# LCDTFT_CTRL_BT817.net
KiCad netlist of a schematic drawn in Altium Designer
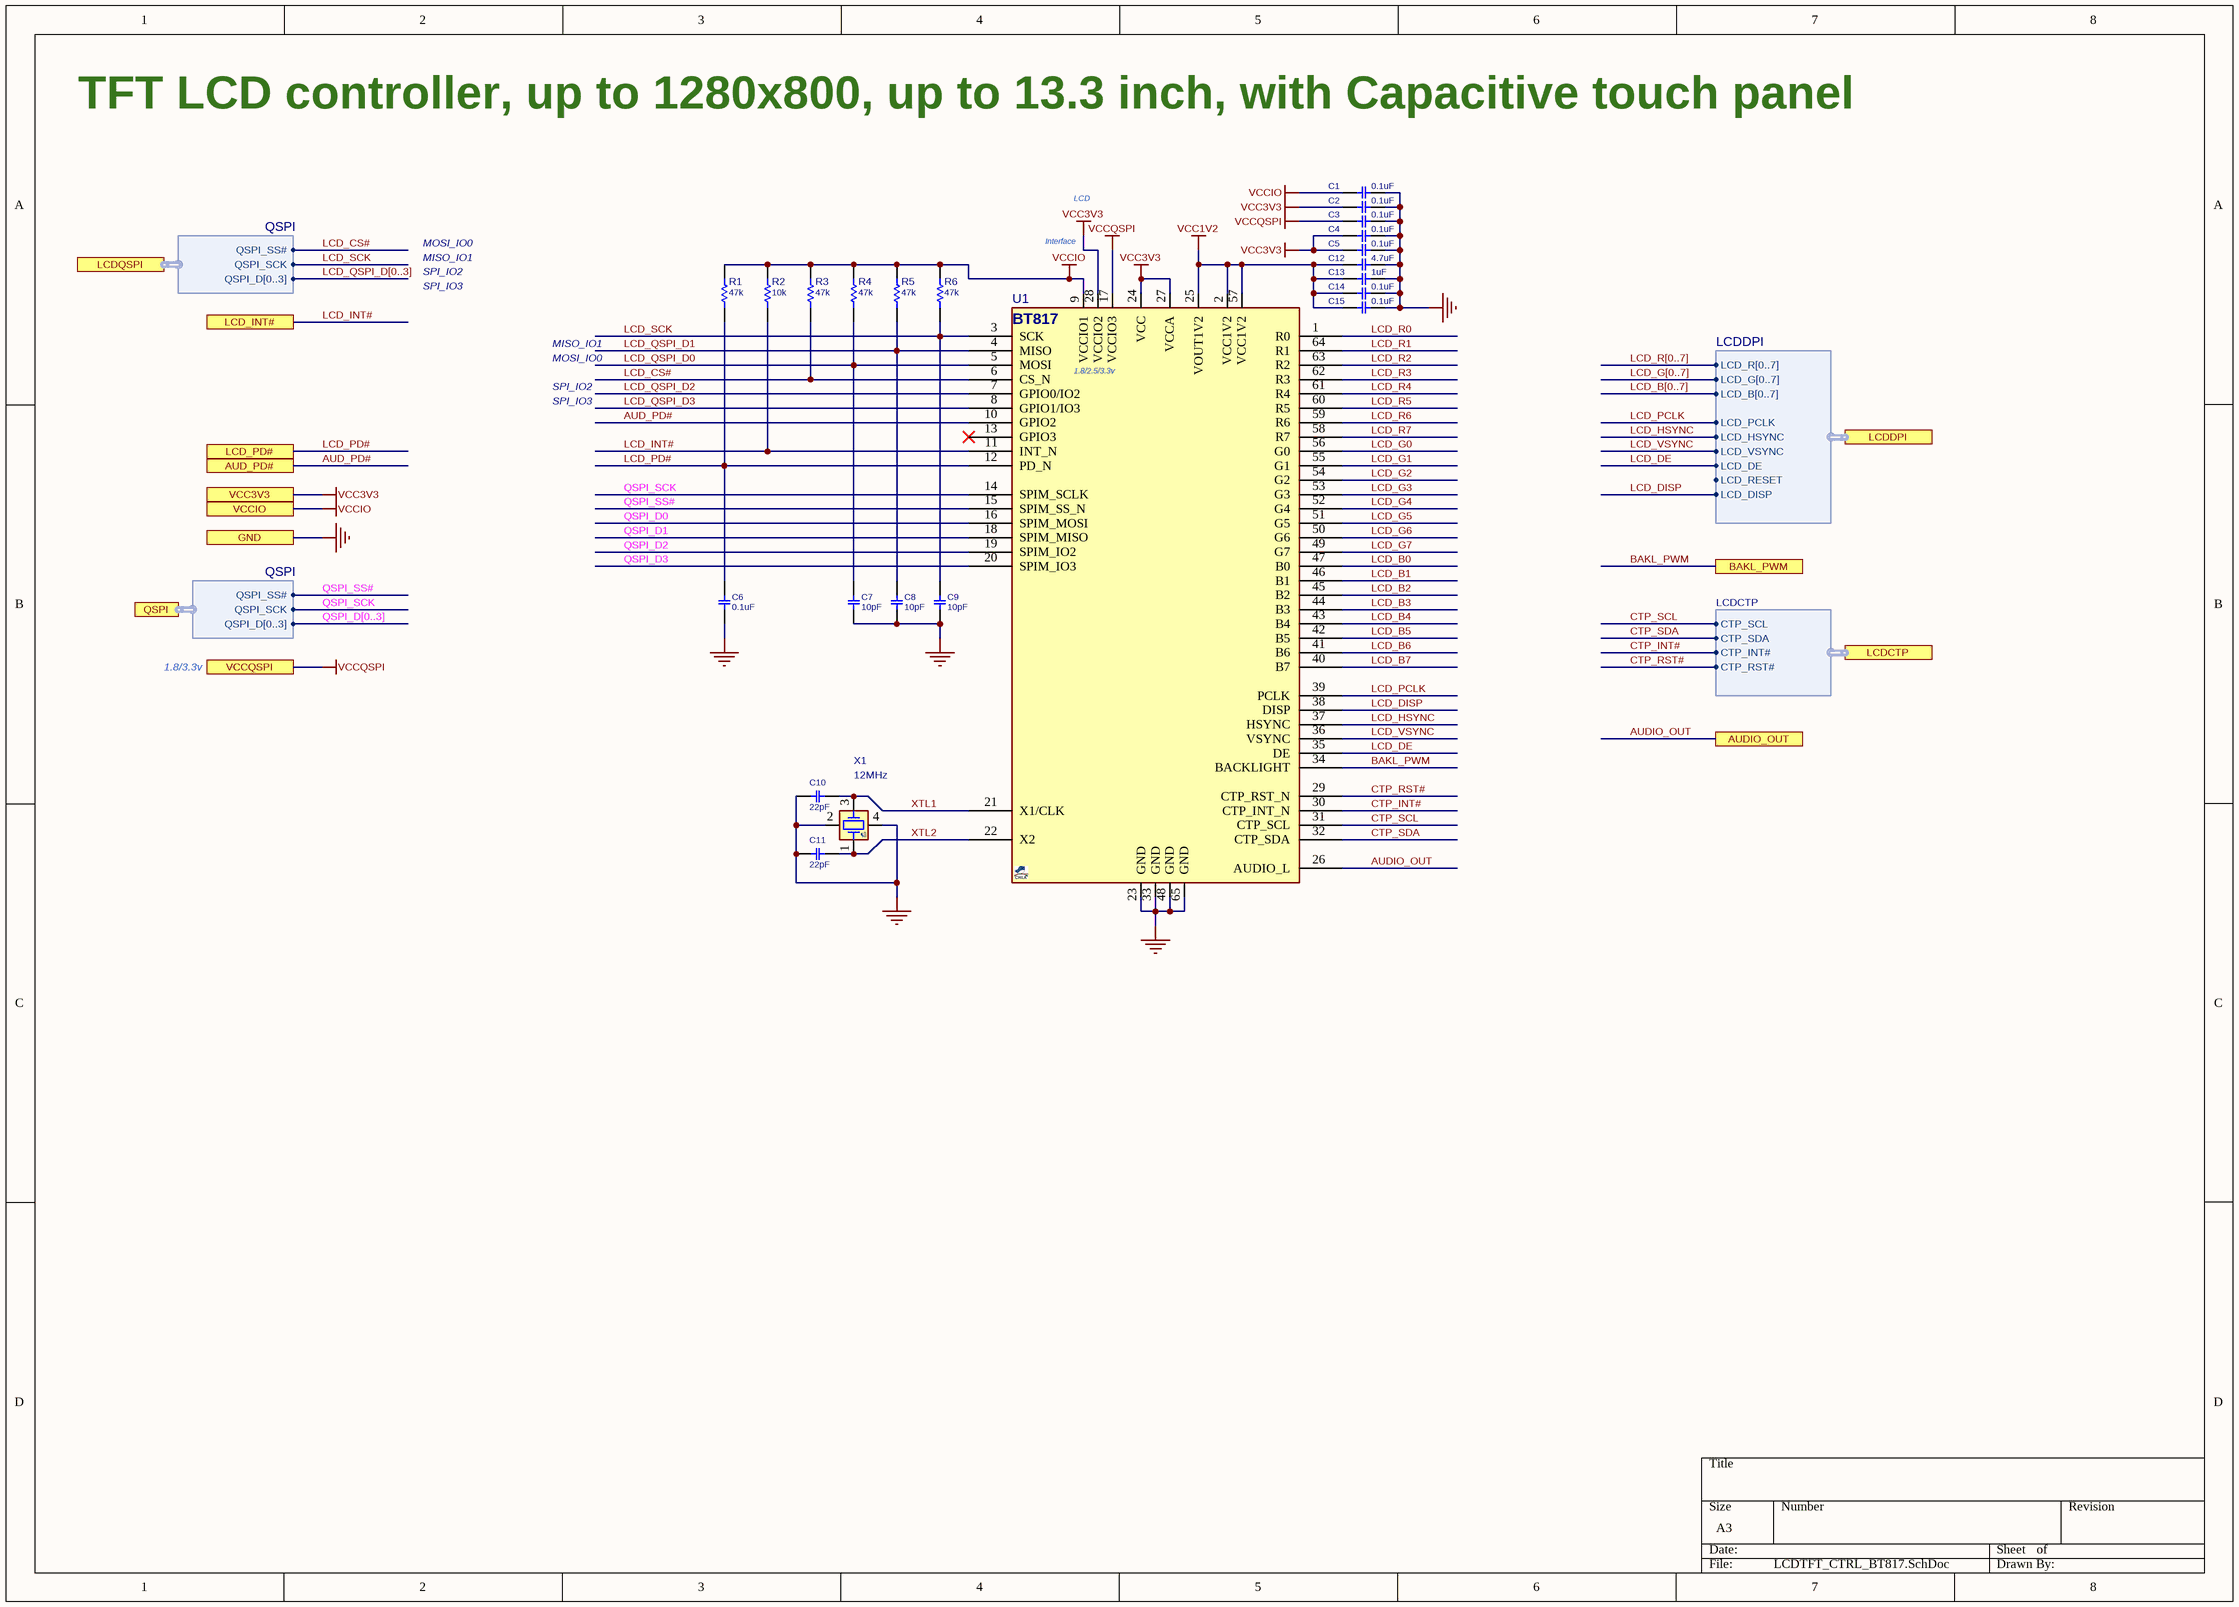
[diagram p0: LCDTFT_CTRL_BT817.SchDoc]

(export (version "E")
  (design (tool "Eeschema 10.0.6"))
  (components
    (comp (ref "C1")
      (value "0.1uF")
      (footprint "C0402")
      (description "CAP, MLCC")
      (fields (field (name "MANF_P#") "GRM155R71H104KE14D") (field (name "MANF") "Murata"))
      (libsource (lib "passive_smd") (part "CAP_SMD_MLCC"))
    )
    (comp (ref "C2")
      (value "0.1uF")
      (footprint "C0402")
      (description "CAP, MLCC")
      (fields (field (name "MANF_P#") "GRM155R71H104KE14D") (field (name "MANF") "Murata"))
      (libsource (lib "passive_smd") (part "CAP_SMD_MLCC"))
    )
    (comp (ref "C3")
      (value "0.1uF")
      (footprint "C0402")
      (description "CAP, MLCC")
      (fields (field (name "MANF_P#") "GRM155R71H104KE14D") (field (name "MANF") "Murata"))
      (libsource (lib "passive_smd") (part "CAP_SMD_MLCC"))
    )
    (comp (ref "C4")
      (value "0.1uF")
      (footprint "C0402")
      (description "CAP, MLCC")
      (fields (field (name "MANF_P#") "GRM155R71H104KE14D") (field (name "MANF") "Murata"))
      (libsource (lib "passive_smd") (part "CAP_SMD_MLCC"))
    )
    (comp (ref "C5")
      (value "0.1uF")
      (footprint "C0402")
      (description "CAP, MLCC")
      (fields (field (name "MANF_P#") "GRM155R71H104KE14D") (field (name "MANF") "Murata"))
      (libsource (lib "passive_smd") (part "CAP_SMD_MLCC"))
    )
    (comp (ref "C6")
      (value "0.1uF")
      (footprint "C0402")
      (description "CAP, MLCC")
      (fields (field (name "MANF_P#") "GRM155R71H104KE14D") (field (name "MANF") "Murata"))
      (libsource (lib "passive_smd") (part "CAP_SMD_MLCC"))
    )
    (comp (ref "C7")
      (value "10pF")
      (footprint "C0402")
      (description "CAP, MLCC")
      (libsource (lib "passive_smd") (part "CAP_SMD_MLCC"))
    )
    (comp (ref "C8")
      (value "10pF")
      (footprint "C0402")
      (description "CAP, MLCC")
      (libsource (lib "passive_smd") (part "CAP_SMD_MLCC"))
    )
    (comp (ref "C9")
      (value "10pF")
      (footprint "C0402")
      (description "CAP, MLCC")
      (libsource (lib "passive_smd") (part "CAP_SMD_MLCC"))
    )
    (comp (ref "C10")
      (value "22pF")
      (footprint "C0402")
      (description "CAP, MLCC")
      (libsource (lib "passive_smd") (part "CAP_SMD_MLCC"))
    )
    (comp (ref "C11")
      (value "22pF")
      (footprint "C0402")
      (description "CAP, MLCC")
      (libsource (lib "passive_smd") (part "CAP_SMD_MLCC"))
    )
    (comp (ref "C12")
      (value "4.7uF")
      (footprint "C0402")
      (description "CAP, MLCC")
      (libsource (lib "passive_smd") (part "CAP_SMD_MLCC"))
    )
    (comp (ref "C13")
      (value "1uF")
      (footprint "C0402")
      (description "CAP, MLCC")
      (libsource (lib "passive_smd") (part "CAP_SMD_MLCC"))
    )
    (comp (ref "C14")
      (value "0.1uF")
      (footprint "C0402")
      (description "CAP, MLCC")
      (fields (field (name "MANF_P#") "GRM155R71H104KE14D") (field (name "MANF") "Murata"))
      (libsource (lib "passive_smd") (part "CAP_SMD_MLCC"))
    )
    (comp (ref "C15")
      (value "0.1uF")
      (footprint "C0402")
      (description "CAP, MLCC")
      (fields (field (name "MANF_P#") "GRM155R71H104KE14D") (field (name "MANF") "Murata"))
      (libsource (lib "passive_smd") (part "CAP_SMD_MLCC"))
    )
    (comp (ref "R1")
      (value "47k")
      (footprint "R0402")
      (description "RESISTOR, SMD")
      (libsource (lib "passive_res_smd") (part "RES_SMD"))
    )
    (comp (ref "R2")
      (value "10k")
      (footprint "R0402")
      (description "RESISTOR, SMD")
      (libsource (lib "passive_res_smd") (part "RES_SMD"))
    )
    (comp (ref "R3")
      (value "47k")
      (footprint "R0402")
      (description "RESISTOR, SMD")
      (libsource (lib "passive_res_smd") (part "RES_SMD"))
    )
    (comp (ref "R4")
      (value "47k")
      (footprint "R0402")
      (description "RESISTOR, SMD")
      (libsource (lib "passive_res_smd") (part "RES_SMD"))
    )
    (comp (ref "R5")
      (value "47k")
      (footprint "R0402")
      (description "RESISTOR, SMD")
      (libsource (lib "passive_res_smd") (part "RES_SMD"))
    )
    (comp (ref "R6")
      (value "47k")
      (footprint "R0402")
      (description "RESISTOR, SMD")
      (libsource (lib "passive_res_smd") (part "RES_SMD"))
    )
    (comp (ref "U1")
      (value "BT817")
      (footprint "QFN50_64T")
      (description "LCD Display Controller, Embedded Video Engine, 1280X800, QFN-64")
      (fields (field (name "MANF") "FTDI/Bridgetek") (field (name "MANF_P#") "BT817Q"))
      (libsource (lib "lcdtft_controller") (part "BT817_QFN64"))
    )
    (comp (ref "X1")
      (value "12MHz")
      (footprint "XTL_4_3225")
      (description "Crystal 12MHz")
      (fields (field (name "MANF") "ECS") (field (name "MANF_P#") "ECS-120-18-33-JEM-TR"))
      (libsource (lib "crystal") (part "XTL_4_12MHz_3225"))
    )
  )
  (nets
    (net (code "4") (name "/AUDIO_OUT") (class "Default")
      (node (ref "U1") (pin "26") (pinfunction "AUDIO_L_26") (pintype "passive"))
    )
    (net (code "5") (name "/AUD_PD#") (class "Default")
      (node (ref "U1") (pin "10") (pinfunction "GPIO2_10") (pintype "passive"))
    )
    (net (code "6") (name "/BAKL_PWM") (class "Default")
      (node (ref "U1") (pin "34") (pinfunction "BACKLIGHT_34") (pintype "passive"))
    )
    (net (code "7") (name "/CTP_INT#") (class "Default")
      (node (ref "U1") (pin "30") (pinfunction "CTP_INT_N_30") (pintype "passive"))
    )
    (net (code "8") (name "/CTP_RST#") (class "Default")
      (node (ref "U1") (pin "29") (pinfunction "CTP_RST_N_29") (pintype "passive"))
    )
    (net (code "9") (name "/CTP_SCL") (class "Default")
      (node (ref "U1") (pin "31") (pinfunction "CTP_SCL_31") (pintype "passive"))
    )
    (net (code "10") (name "/CTP_SDA") (class "Default")
      (node (ref "U1") (pin "32") (pinfunction "CTP_SDA_32") (pintype "passive"))
    )
    (net (code "11") (name "/LCD_B0") (class "Default")
      (node (ref "U1") (pin "47") (pinfunction "B0_47") (pintype "passive"))
    )
    (net (code "12") (name "/LCD_B1") (class "Default")
      (node (ref "U1") (pin "46") (pinfunction "B1_46") (pintype "passive"))
    )
    (net (code "13") (name "/LCD_B2") (class "Default")
      (node (ref "U1") (pin "45") (pinfunction "B2_45") (pintype "passive"))
    )
    (net (code "14") (name "/LCD_B3") (class "Default")
      (node (ref "U1") (pin "44") (pinfunction "B3_44") (pintype "passive"))
    )
    (net (code "15") (name "/LCD_B4") (class "Default")
      (node (ref "U1") (pin "43") (pinfunction "B4_43") (pintype "passive"))
    )
    (net (code "16") (name "/LCD_B5") (class "Default")
      (node (ref "U1") (pin "42") (pinfunction "B5_42") (pintype "passive"))
    )
    (net (code "17") (name "/LCD_B6") (class "Default")
      (node (ref "U1") (pin "41") (pinfunction "B6_41") (pintype "passive"))
    )
    (net (code "18") (name "/LCD_B7") (class "Default")
      (node (ref "U1") (pin "40") (pinfunction "B7_40") (pintype "passive"))
    )
    (net (code "20") (name "/LCD_CS#") (class "Default")
      (node (ref "R3") (pin "2") (pinfunction "2_2") (pintype "passive"))
      (node (ref "U1") (pin "6") (pinfunction "CS_N_6") (pintype "passive"))
    )
    (net (code "21") (name "/LCD_DE") (class "Default")
      (node (ref "U1") (pin "35") (pinfunction "DE_35") (pintype "passive"))
    )
    (net (code "22") (name "/LCD_DISP") (class "Default")
      (node (ref "U1") (pin "38") (pinfunction "DISP_38") (pintype "passive"))
    )
    (net (code "23") (name "/LCD_G0") (class "Default")
      (node (ref "U1") (pin "56") (pinfunction "G0_56") (pintype "passive"))
    )
    (net (code "24") (name "/LCD_G1") (class "Default")
      (node (ref "U1") (pin "55") (pinfunction "G1_55") (pintype "passive"))
    )
    (net (code "25") (name "/LCD_G2") (class "Default")
      (node (ref "U1") (pin "54") (pinfunction "G2_54") (pintype "passive"))
    )
    (net (code "26") (name "/LCD_G3") (class "Default")
      (node (ref "U1") (pin "53") (pinfunction "G3_53") (pintype "passive"))
    )
    (net (code "27") (name "/LCD_G4") (class "Default")
      (node (ref "U1") (pin "52") (pinfunction "G4_52") (pintype "passive"))
    )
    (net (code "28") (name "/LCD_G5") (class "Default")
      (node (ref "U1") (pin "51") (pinfunction "G5_51") (pintype "passive"))
    )
    (net (code "29") (name "/LCD_G6") (class "Default")
      (node (ref "U1") (pin "50") (pinfunction "G6_50") (pintype "passive"))
    )
    (net (code "30") (name "/LCD_G7") (class "Default")
      (node (ref "U1") (pin "49") (pinfunction "G7_49") (pintype "passive"))
    )
    (net (code "32") (name "/LCD_HSYNC") (class "Default")
      (node (ref "U1") (pin "37") (pinfunction "HSYNC_37") (pintype "passive"))
    )
    (net (code "33") (name "/LCD_INT#") (class "Default")
      (node (ref "R2") (pin "2") (pinfunction "2_2") (pintype "passive"))
      (node (ref "U1") (pin "11") (pinfunction "INT_N_11") (pintype "passive"))
    )
    (net (code "34") (name "/LCD_PCLK") (class "Default")
      (node (ref "U1") (pin "39") (pinfunction "PCLK_39") (pintype "passive"))
    )
    (net (code "35") (name "/LCD_PD#") (class "Default")
      (node (ref "C6") (pin "1") (pinfunction "1_1") (pintype "passive"))
      (node (ref "R1") (pin "2") (pinfunction "2_2") (pintype "passive"))
      (node (ref "U1") (pin "12") (pinfunction "PD_N_12") (pintype "passive"))
    )
    (net (code "36") (name "/LCD_QSPI_D0") (class "Default")
      (node (ref "C7") (pin "1") (pinfunction "1_1") (pintype "passive"))
      (node (ref "R4") (pin "2") (pinfunction "2_2") (pintype "passive"))
      (node (ref "U1") (pin "5") (pinfunction "MOSI_5") (pintype "passive"))
    )
    (net (code "37") (name "/LCD_QSPI_D1") (class "Default")
      (node (ref "C8") (pin "1") (pinfunction "1_1") (pintype "passive"))
      (node (ref "R5") (pin "2") (pinfunction "2_2") (pintype "passive"))
      (node (ref "U1") (pin "4") (pinfunction "MISO_4") (pintype "passive"))
    )
    (net (code "38") (name "/LCD_QSPI_D2") (class "Default")
      (node (ref "U1") (pin "7") (pinfunction "GPIO0/IO2_7") (pintype "passive"))
    )
    (net (code "39") (name "/LCD_QSPI_D3") (class "Default")
      (node (ref "U1") (pin "8") (pinfunction "GPIO1/IO3_8") (pintype "passive"))
    )
    (net (code "41") (name "/LCD_R0") (class "Default")
      (node (ref "U1") (pin "1") (pinfunction "R0_1") (pintype "passive"))
    )
    (net (code "42") (name "/LCD_R1") (class "Default")
      (node (ref "U1") (pin "64") (pinfunction "R1_64") (pintype "passive"))
    )
    (net (code "43") (name "/LCD_R2") (class "Default")
      (node (ref "U1") (pin "63") (pinfunction "R2_63") (pintype "passive"))
    )
    (net (code "44") (name "/LCD_R3") (class "Default")
      (node (ref "U1") (pin "62") (pinfunction "R3_62") (pintype "passive"))
    )
    (net (code "45") (name "/LCD_R4") (class "Default")
      (node (ref "U1") (pin "61") (pinfunction "R4_61") (pintype "passive"))
    )
    (net (code "46") (name "/LCD_R5") (class "Default")
      (node (ref "U1") (pin "60") (pinfunction "R5_60") (pintype "passive"))
    )
    (net (code "47") (name "/LCD_R6") (class "Default")
      (node (ref "U1") (pin "59") (pinfunction "R6_59") (pintype "passive"))
    )
    (net (code "48") (name "/LCD_R7") (class "Default")
      (node (ref "U1") (pin "58") (pinfunction "R7_58") (pintype "passive"))
    )
    (net (code "50") (name "/LCD_SCK") (class "Default")
      (node (ref "C9") (pin "1") (pinfunction "1_1") (pintype "passive"))
      (node (ref "R6") (pin "2") (pinfunction "2_2") (pintype "passive"))
      (node (ref "U1") (pin "3") (pinfunction "SCK_3") (pintype "passive"))
    )
    (net (code "51") (name "/LCD_VSYNC") (class "Default")
      (node (ref "U1") (pin "36") (pinfunction "VSYNC_36") (pintype "passive"))
    )
    (net (code "52") (name "/QSPI_D0") (class "Default")
      (node (ref "U1") (pin "16") (pinfunction "SPIM_MOSI_16") (pintype "passive"))
    )
    (net (code "53") (name "/QSPI_D1") (class "Default")
      (node (ref "U1") (pin "18") (pinfunction "SPIM_MISO_18") (pintype "passive"))
    )
    (net (code "54") (name "/QSPI_D2") (class "Default")
      (node (ref "U1") (pin "19") (pinfunction "SPIM_IO2_19") (pintype "passive"))
    )
    (net (code "55") (name "/QSPI_D3") (class "Default")
      (node (ref "U1") (pin "20") (pinfunction "SPIM_IO3_20") (pintype "passive"))
    )
    (net (code "57") (name "/QSPI_SCK") (class "Default")
      (node (ref "U1") (pin "14") (pinfunction "SPIM_SCLK_14") (pintype "passive"))
    )
    (net (code "58") (name "/QSPI_SS#") (class "Default")
      (node (ref "U1") (pin "15") (pinfunction "SPIM_SS_N_15") (pintype "passive"))
    )
    (net (code "59") (name "/XTL1") (class "Default")
      (node (ref "C10") (pin "2") (pinfunction "2_2") (pintype "passive"))
      (node (ref "U1") (pin "21") (pinfunction "X1/CLK_21") (pintype "passive"))
      (node (ref "X1") (pin "3") (pinfunction "2_3") (pintype "passive"))
    )
    (net (code "60") (name "/XTL2") (class "Default")
      (node (ref "C11") (pin "1") (pinfunction "1_1") (pintype "passive"))
      (node (ref "U1") (pin "22") (pinfunction "X2_22") (pintype "passive"))
      (node (ref "X1") (pin "1") (pinfunction "1_1") (pintype "passive"))
    )
    (net (code "64") (name "GND") (class "Default")
      (node (ref "C1") (pin "1") (pinfunction "1_1") (pintype "passive"))
      (node (ref "C10") (pin "1") (pinfunction "1_1") (pintype "passive"))
      (node (ref "C11") (pin "2") (pinfunction "2_2") (pintype "passive"))
      (node (ref "C12") (pin "1") (pinfunction "1_1") (pintype "passive"))
      (node (ref "C13") (pin "1") (pinfunction "1_1") (pintype "passive"))
      (node (ref "C14") (pin "1") (pinfunction "1_1") (pintype "passive"))
      (node (ref "C15") (pin "1") (pinfunction "1_1") (pintype "passive"))
      (node (ref "C2") (pin "1") (pinfunction "1_1") (pintype "passive"))
      (node (ref "C3") (pin "1") (pinfunction "1_1") (pintype "passive"))
      (node (ref "C4") (pin "1") (pinfunction "1_1") (pintype "passive"))
      (node (ref "C5") (pin "1") (pinfunction "1_1") (pintype "passive"))
      (node (ref "C6") (pin "2") (pinfunction "2_2") (pintype "passive"))
      (node (ref "C7") (pin "2") (pinfunction "2_2") (pintype "passive"))
      (node (ref "C8") (pin "2") (pinfunction "2_2") (pintype "passive"))
      (node (ref "C9") (pin "2") (pinfunction "2_2") (pintype "passive"))
      (node (ref "U1") (pin "23") (pinfunction "GND_23") (pintype "passive"))
      (node (ref "U1") (pin "33") (pinfunction "GND_33") (pintype "passive"))
      (node (ref "U1") (pin "48") (pinfunction "GND_48") (pintype "passive"))
      (node (ref "U1") (pin "65") (pinfunction "GND_65") (pintype "passive"))
      (node (ref "X1") (pin "2") (pinfunction "2_2") (pintype "passive"))
      (node (ref "X1") (pin "4") (pinfunction "4_4") (pintype "passive"))
    )
    (net (code "65") (name "VCC1V2") (class "Default")
      (node (ref "C12") (pin "2") (pinfunction "2_2") (pintype "passive"))
      (node (ref "C13") (pin "2") (pinfunction "2_2") (pintype "passive"))
      (node (ref "C14") (pin "2") (pinfunction "2_2") (pintype "passive"))
      (node (ref "C15") (pin "2") (pinfunction "2_2") (pintype "passive"))
      (node (ref "U1") (pin "2") (pinfunction "VCC1V2_2") (pintype "passive"))
      (node (ref "U1") (pin "25") (pinfunction "VOUT1V2_25") (pintype "passive"))
      (node (ref "U1") (pin "57") (pinfunction "VCC1V2_57") (pintype "passive"))
    )
    (net (code "66") (name "VCC3V3") (class "Default")
      (node (ref "C2") (pin "2") (pinfunction "2_2") (pintype "passive"))
      (node (ref "C4") (pin "2") (pinfunction "2_2") (pintype "passive"))
      (node (ref "C5") (pin "2") (pinfunction "2_2") (pintype "passive"))
      (node (ref "U1") (pin "24") (pinfunction "VCC_24") (pintype "passive"))
      (node (ref "U1") (pin "27") (pinfunction "VCCA_27") (pintype "passive"))
      (node (ref "U1") (pin "28") (pinfunction "VCCIO2_28") (pintype "passive"))
    )
    (net (code "67") (name "VCCIO") (class "Default")
      (node (ref "C1") (pin "2") (pinfunction "2_2") (pintype "passive"))
      (node (ref "R1") (pin "1") (pinfunction "1_1") (pintype "passive"))
      (node (ref "R2") (pin "1") (pinfunction "1_1") (pintype "passive"))
      (node (ref "R3") (pin "1") (pinfunction "1_1") (pintype "passive"))
      (node (ref "R4") (pin "1") (pinfunction "1_1") (pintype "passive"))
      (node (ref "R5") (pin "1") (pinfunction "1_1") (pintype "passive"))
      (node (ref "R6") (pin "1") (pinfunction "1_1") (pintype "passive"))
      (node (ref "U1") (pin "9") (pinfunction "VCCIO1_9") (pintype "passive"))
    )
    (net (code "68") (name "VCCQSPI") (class "Default")
      (node (ref "C3") (pin "2") (pinfunction "2_2") (pintype "passive"))
      (node (ref "U1") (pin "17") (pinfunction "VCCIO3_17") (pintype "passive"))
    )
    (net (code "69") (name "unconnected-(U1-GPIO3-Pad13)") (class "Default")
      (node (ref "U1") (pin "13") (pinfunction "GPIO3_13") (pintype "passive+no_connect"))
    )
  )
)
